# SCH_breakout_board_for_servo_2022-09-03.net
KiCad netlist of a schematic drawn in EasyEDA
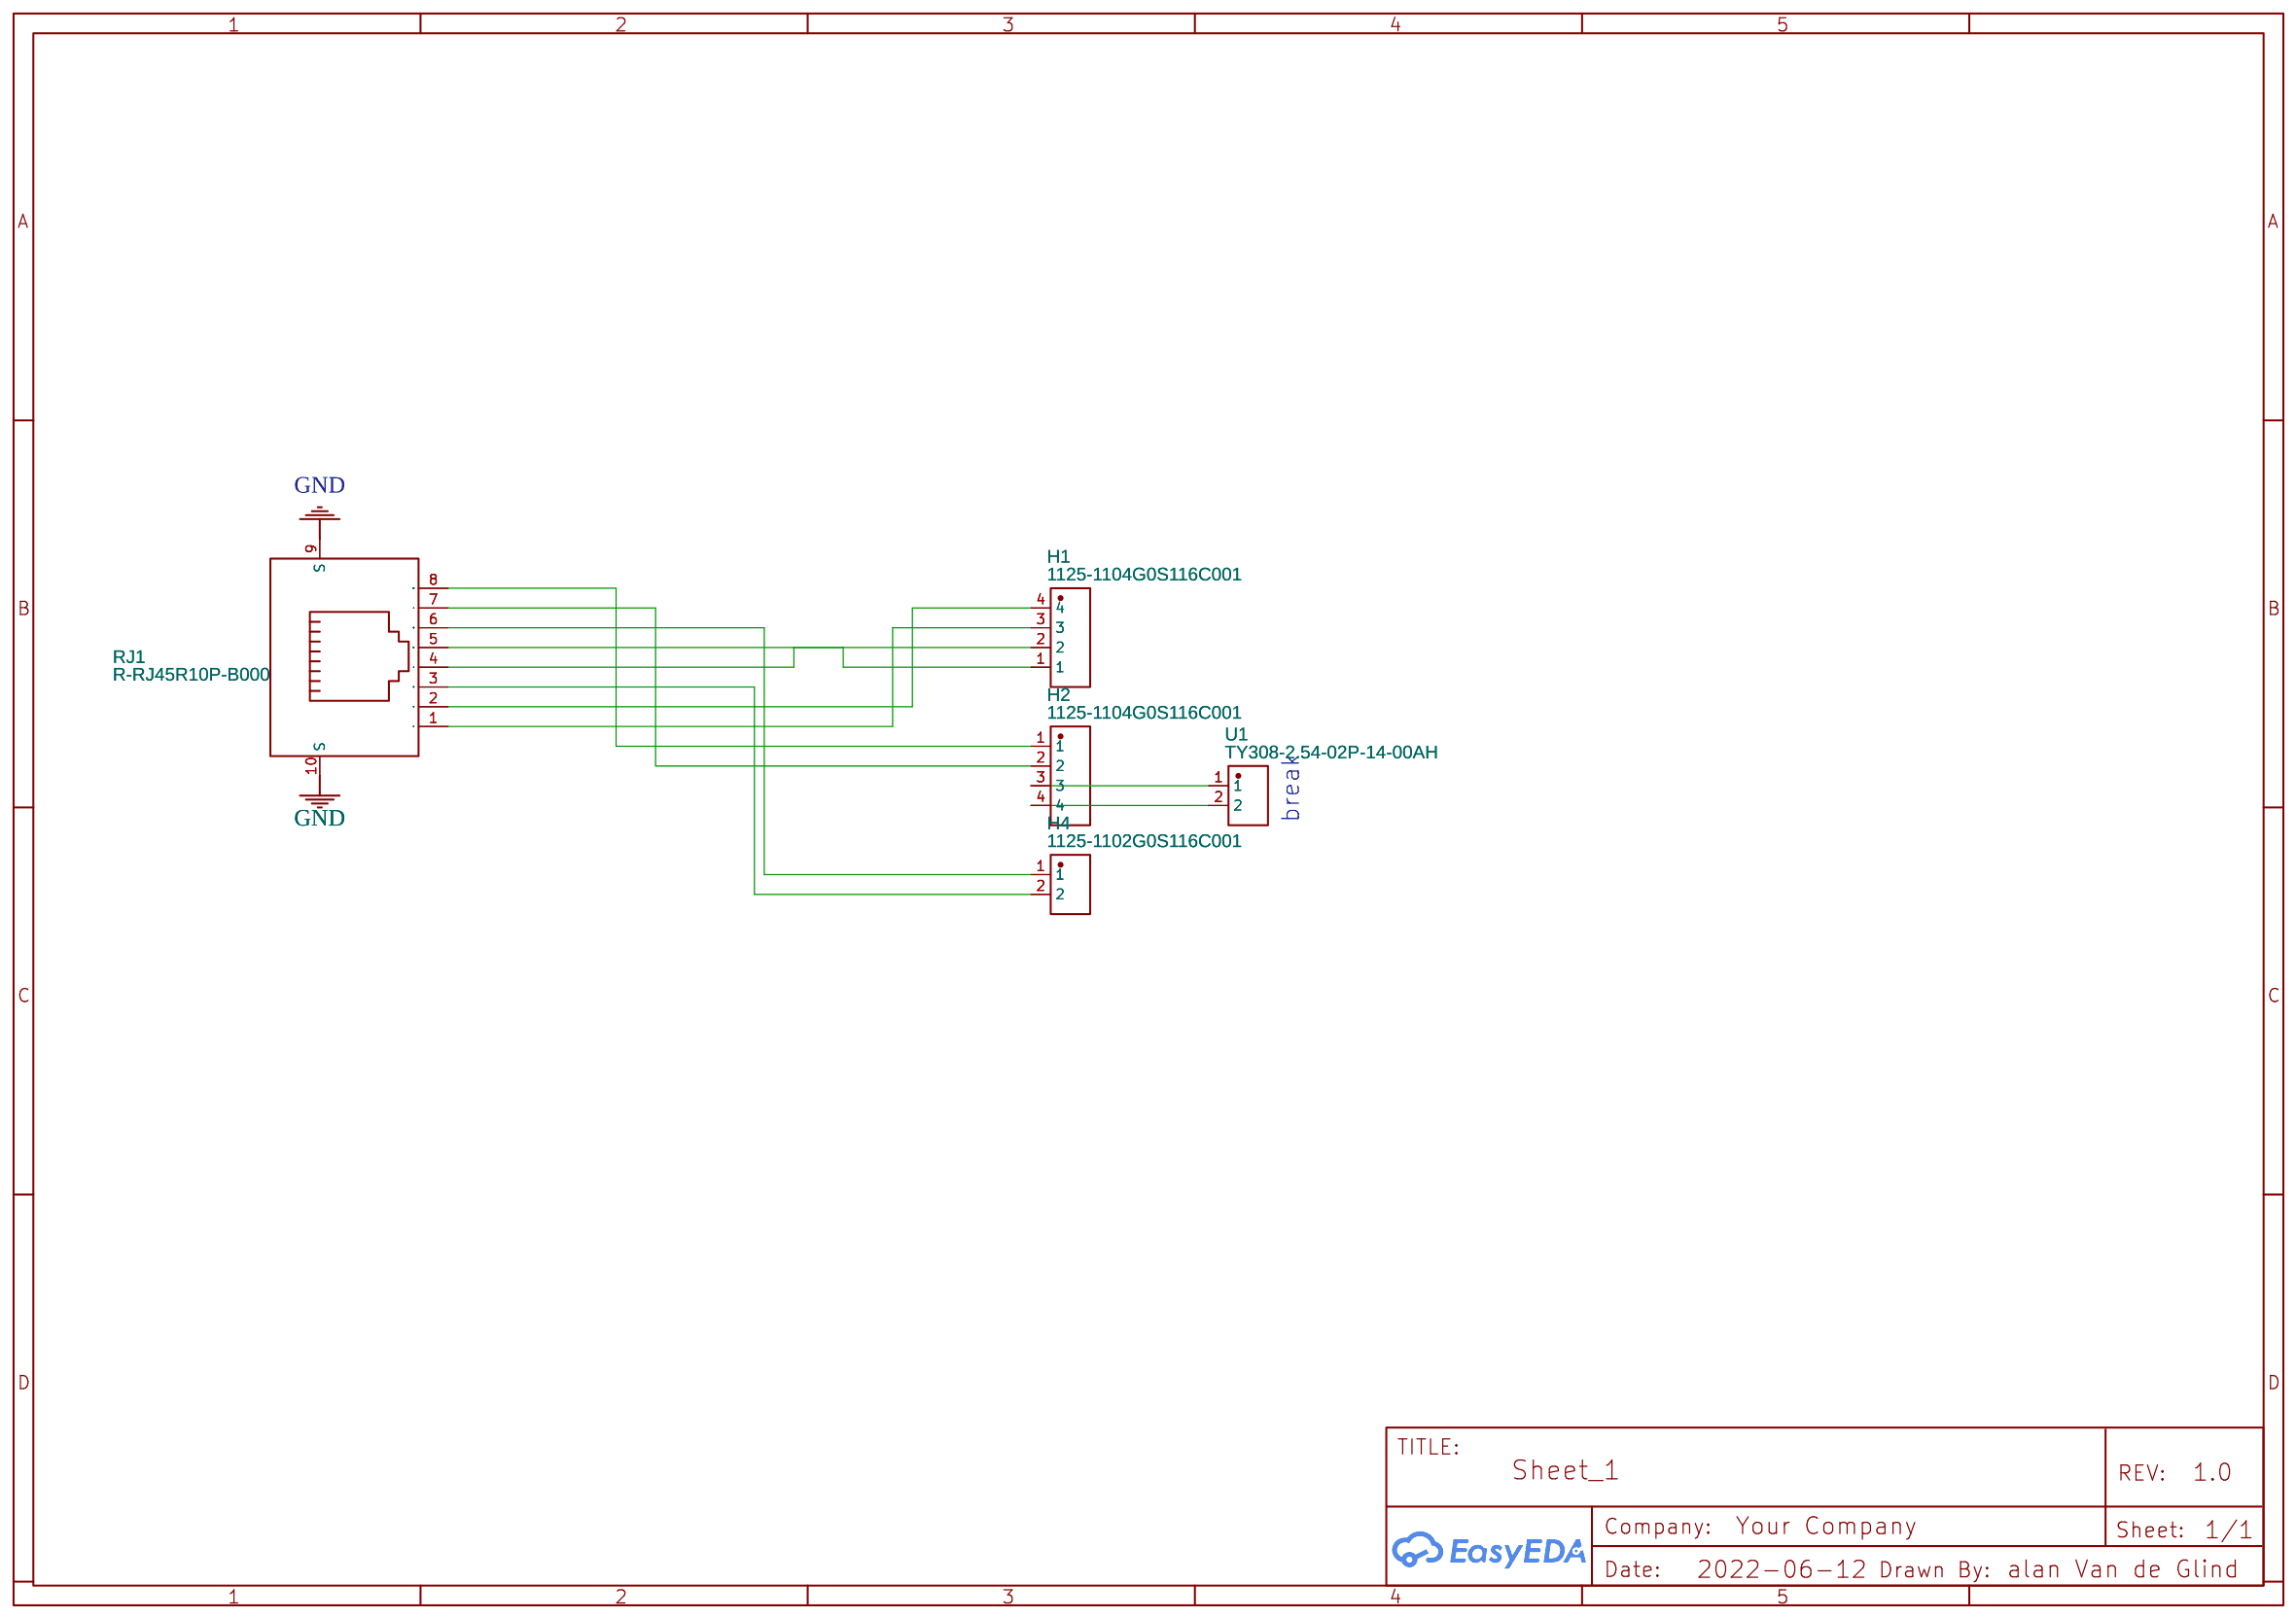
[diagram p0: schematic sheet]

(export (version "E")
  (design (tool "Eeschema 10.0.6"))
  (components
    (comp (ref "H1")
      (value "1125-1104G0S116C001")
      (fields (field (name "BOM_Supplier Part") "C920779"))
      (libsource (lib "") (part "1125-1104G0S116C001"))
    )
    (comp (ref "H2")
      (value "1125-1104G0S116C001")
      (fields (field (name "BOM_Supplier Part") "C920779"))
      (libsource (lib "") (part "1125-1104G0S116C001_1"))
    )
    (comp (ref "H4")
      (value "1125-1102G0S116C001")
      (fields (field (name "BOM_Supplier Part") "C920781"))
      (libsource (lib "") (part "1125-1102G0S116C001"))
    )
    (comp (ref "RJ1")
      (value "R-RJ45R10P-B000")
      (fields (field (name "BOM_Supplier Part") "C386758"))
      (libsource (lib "") (part "R-RJ45R10P-B000"))
    )
    (comp (ref "U1")
      (value "TY308-2.54-02P-14-00AH")
      (fields (field (name "BOM_Supplier Part") "C2840316"))
      (libsource (lib "") (part "TY308-2.54-02P-14-00AH"))
    )
  )
  (nets
    (net (code "1") (name "GND") (class "Default")
      (node (ref "RJ1") (pin "10") (pinfunction "S_10") (pintype "unspecified"))
      (node (ref "RJ1") (pin "9") (pinfunction "S_9") (pintype "unspecified"))
    )
    (net (code "2") (name "Net-(H1-Pad1)") (class "Default")
      (node (ref "H1") (pin "1") (pinfunction "1_1") (pintype "unspecified"))
      (node (ref "RJ1") (pin "5") (pinfunction "5_5") (pintype "unspecified"))
    )
    (net (code "3") (name "Net-(H1-Pad2)") (class "Default")
      (node (ref "H1") (pin "2") (pinfunction "2_2") (pintype "unspecified"))
      (node (ref "RJ1") (pin "4") (pinfunction "4_4") (pintype "unspecified"))
    )
    (net (code "4") (name "Net-(H1-Pad3)") (class "Default")
      (node (ref "H1") (pin "3") (pinfunction "3_3") (pintype "unspecified"))
      (node (ref "RJ1") (pin "1") (pinfunction "1_1") (pintype "unspecified"))
    )
    (net (code "5") (name "Net-(H1-Pad4)") (class "Default")
      (node (ref "H1") (pin "4") (pinfunction "4_4") (pintype "unspecified"))
      (node (ref "RJ1") (pin "2") (pinfunction "2_2") (pintype "unspecified"))
    )
    (net (code "6") (name "Net-(H2-Pad1)") (class "Default")
      (node (ref "H2") (pin "1") (pinfunction "1_1") (pintype "unspecified"))
      (node (ref "RJ1") (pin "8") (pinfunction "8_8") (pintype "unspecified"))
    )
    (net (code "7") (name "Net-(H2-Pad2)") (class "Default")
      (node (ref "H2") (pin "2") (pinfunction "2_2") (pintype "unspecified"))
      (node (ref "RJ1") (pin "7") (pinfunction "7_7") (pintype "unspecified"))
    )
    (net (code "8") (name "Net-(H2-Pad3)") (class "Default")
      (node (ref "H2") (pin "3") (pinfunction "3_3") (pintype "unspecified"))
      (node (ref "U1") (pin "1") (pinfunction "1_1") (pintype "unspecified"))
    )
    (net (code "9") (name "Net-(H2-Pad4)") (class "Default")
      (node (ref "H2") (pin "4") (pinfunction "4_4") (pintype "unspecified"))
      (node (ref "U1") (pin "2") (pinfunction "2_2") (pintype "unspecified"))
    )
    (net (code "10") (name "Net-(H4-Pad1)") (class "Default")
      (node (ref "H4") (pin "1") (pinfunction "1_1") (pintype "unspecified"))
      (node (ref "RJ1") (pin "6") (pinfunction "6_6") (pintype "unspecified"))
    )
    (net (code "11") (name "Net-(H4-Pad2)") (class "Default")
      (node (ref "H4") (pin "2") (pinfunction "2_2") (pintype "unspecified"))
      (node (ref "RJ1") (pin "3") (pinfunction "3_3") (pintype "unspecified"))
    )
  )
)
